# M191C.net
KiCad netlist of a schematic drawn in EAGLE
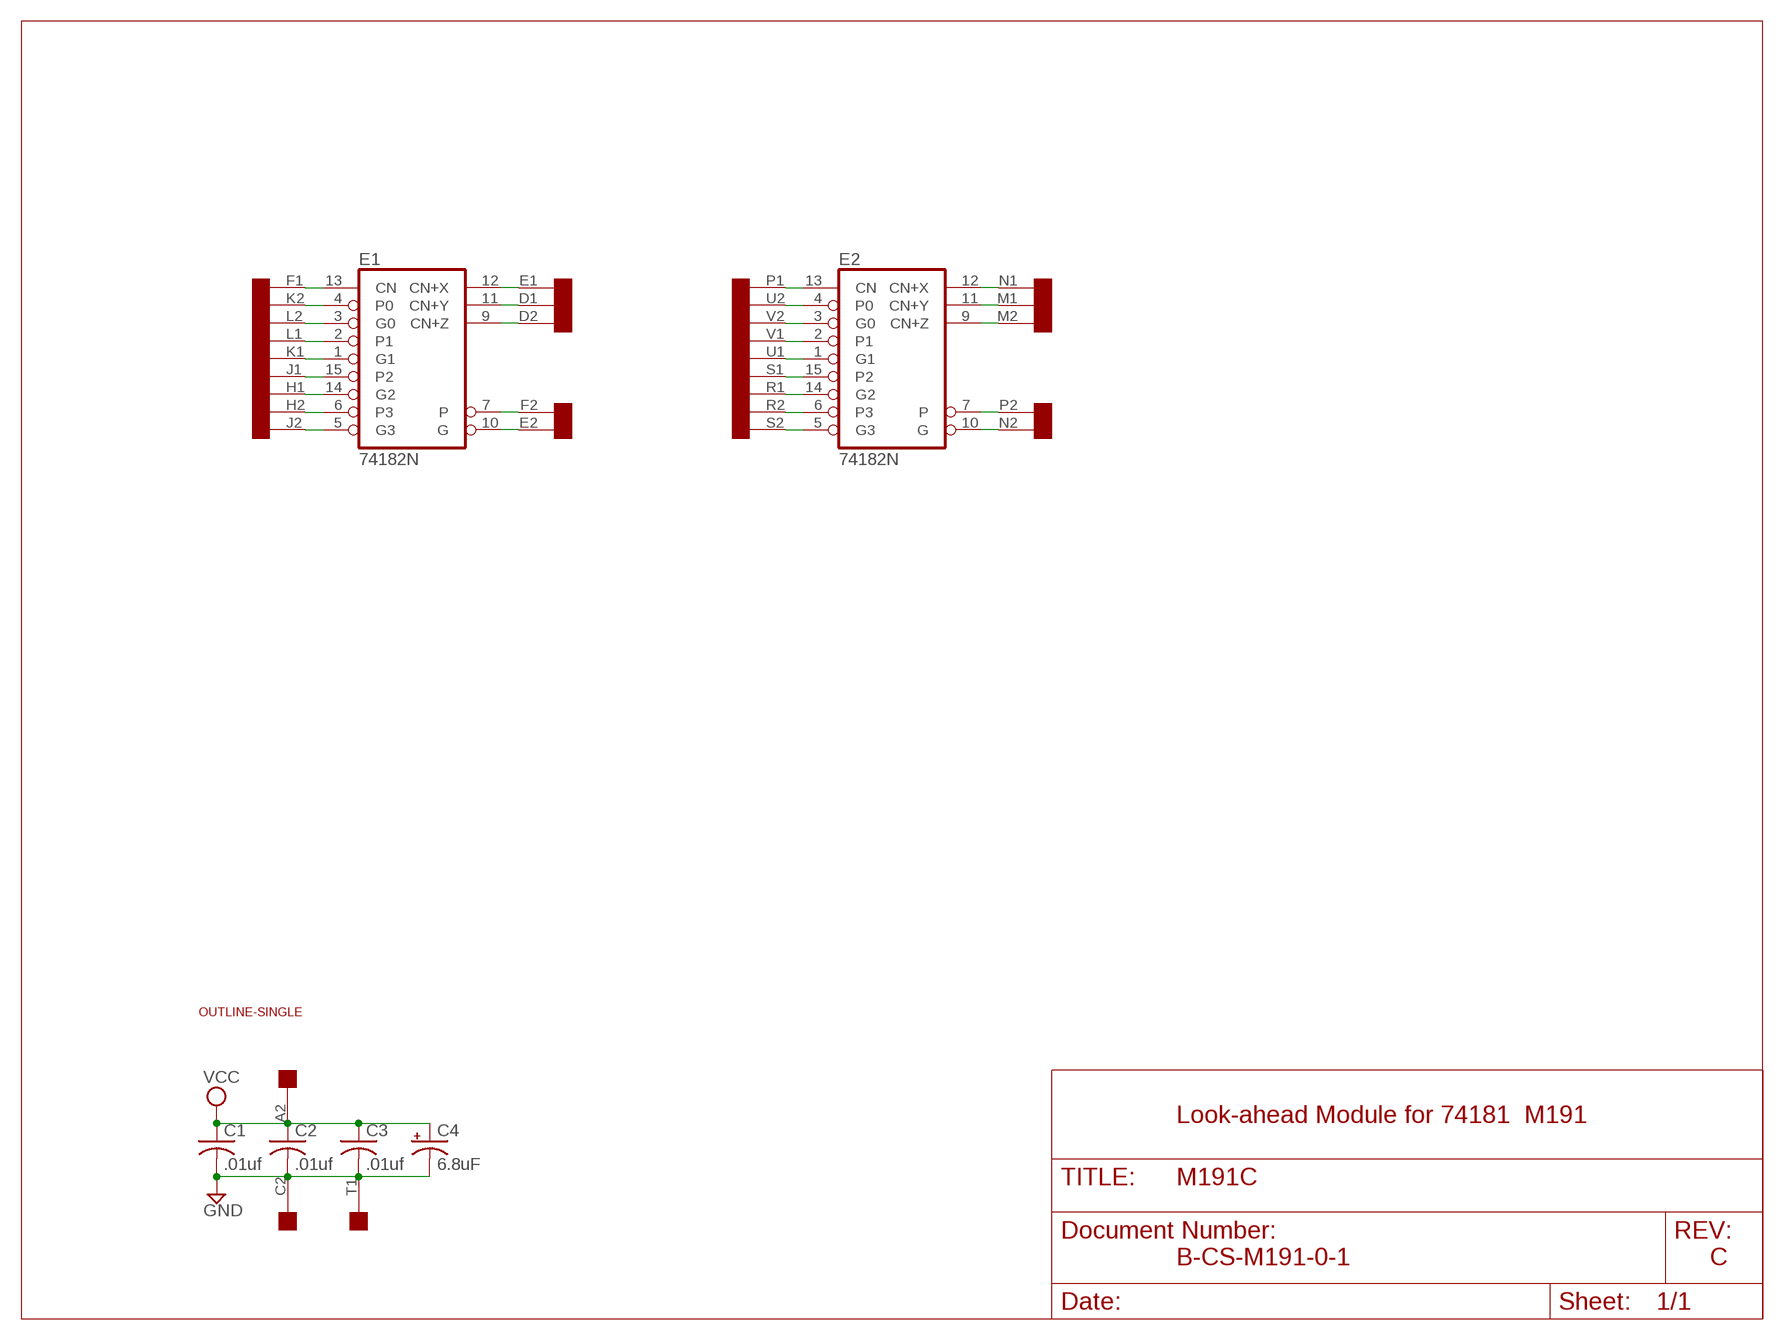
[diagram p0: schematic, sheet 1]

(export (version "E")
  (design (tool "Eeschema 10.0.6"))
  (components
    (comp (ref "C1")
      (value ".01uf")
      (footprint "eagle-import:C050-025X075")
      (libsource (lib "eagle-import") (part "C-US050-025X075"))
    )
    (comp (ref "C2")
      (value ".01uf")
      (footprint "eagle-import:C050-025X075")
      (libsource (lib "eagle-import") (part "C-US050-025X075"))
    )
    (comp (ref "C3")
      (value ".01uf")
      (footprint "eagle-import:C050-025X075")
      (libsource (lib "eagle-import") (part "C-US050-025X075"))
    )
    (comp (ref "C4")
      (value "6.8uF")
      (footprint "eagle-import:E22-6")
      (libsource (lib "eagle-import") (part "CPOL-USE22-6AXIAL"))
    )
    (comp (ref "E1")
      (value "74182N")
      (footprint "eagle-import:DIL16")
      (libsource (lib "eagle-import") (part "74182NS"))
    )
    (comp (ref "E2")
      (value "74182N")
      (footprint "eagle-import:DIL16")
      (libsource (lib "eagle-import") (part "74182NS"))
    )
    (comp (ref "U$1")
      (value "OUTLINE-SINGLE")
      (footprint "eagle-import:SINGLE")
      (libsource (lib "eagle-import") (part "OUTLINE-SINGLE"))
    )
    (comp (ref "U$2")
      (value "EDGE-2CONNECTOR")
      (footprint "eagle-import:EDGE-CON2")
      (libsource (lib "eagle-import") (part "EDGE-2CONNECTOR"))
    )
  )
  (nets
    (net (code "1") (name "GND") (class "Default")
      (node (ref "C1") (pin "2") (pinfunction "2_2") (pintype "passive"))
      (node (ref "C2") (pin "2") (pinfunction "2_2") (pintype "passive"))
      (node (ref "C3") (pin "2") (pinfunction "2_2") (pintype "passive"))
      (node (ref "C4") (pin "-") (pinfunction "-_-") (pintype "passive"))
      (node (ref "U$2") (pin "C2") (pinfunction "1_C2") (pintype "bidirectional"))
      (node (ref "U$2") (pin "T1") (pinfunction "1_T1") (pintype "bidirectional"))
    )
    (net (code "2") (name "Net-(E1A-CN)") (class "Default")
      (node (ref "E1") (pin "13") (pinfunction "CN_13") (pintype "input"))
      (node (ref "U$2") (pin "F1") (pinfunction "1_F1") (pintype "bidirectional"))
    )
    (net (code "3") (name "Net-(E1A-CN+X)") (class "Default")
      (node (ref "E1") (pin "12") (pinfunction "CN+X_12") (pintype "output"))
      (node (ref "U$2") (pin "E1") (pinfunction "1_E1") (pintype "bidirectional"))
    )
    (net (code "4") (name "Net-(E1A-CN+Y)") (class "Default")
      (node (ref "E1") (pin "11") (pinfunction "CN+Y_11") (pintype "output"))
      (node (ref "U$2") (pin "D1") (pinfunction "1_D1") (pintype "bidirectional"))
    )
    (net (code "5") (name "Net-(E1A-CN+Z)") (class "Default")
      (node (ref "E1") (pin "9") (pinfunction "CN+Z_9") (pintype "output"))
      (node (ref "U$2") (pin "D2") (pinfunction "1_D2") (pintype "bidirectional"))
    )
    (net (code "6") (name "Net-(E1A-G)") (class "Default")
      (node (ref "E1") (pin "10") (pinfunction "G_10") (pintype "output"))
      (node (ref "U$2") (pin "E2") (pinfunction "1_E2") (pintype "bidirectional"))
    )
    (net (code "7") (name "Net-(E1A-G0)") (class "Default")
      (node (ref "E1") (pin "3") (pinfunction "G0_3") (pintype "input"))
      (node (ref "U$2") (pin "L2") (pinfunction "1_L2") (pintype "bidirectional"))
    )
    (net (code "8") (name "Net-(E1A-G1)") (class "Default")
      (node (ref "E1") (pin "1") (pinfunction "G1_1") (pintype "input"))
      (node (ref "U$2") (pin "K1") (pinfunction "1_K1") (pintype "bidirectional"))
    )
    (net (code "9") (name "Net-(E1A-G2)") (class "Default")
      (node (ref "E1") (pin "14") (pinfunction "G2_14") (pintype "input"))
      (node (ref "U$2") (pin "H1") (pinfunction "1_H1") (pintype "bidirectional"))
    )
    (net (code "10") (name "Net-(E1A-G3)") (class "Default")
      (node (ref "E1") (pin "5") (pinfunction "G3_5") (pintype "input"))
      (node (ref "U$2") (pin "J2") (pinfunction "1_J2") (pintype "bidirectional"))
    )
    (net (code "11") (name "Net-(E1A-P)") (class "Default")
      (node (ref "E1") (pin "7") (pinfunction "P_7") (pintype "output"))
      (node (ref "U$2") (pin "F2") (pinfunction "1_F2") (pintype "bidirectional"))
    )
    (net (code "12") (name "Net-(E1A-P0)") (class "Default")
      (node (ref "E1") (pin "4") (pinfunction "P0_4") (pintype "input"))
      (node (ref "U$2") (pin "K2") (pinfunction "1_K2") (pintype "bidirectional"))
    )
    (net (code "13") (name "Net-(E1A-P1)") (class "Default")
      (node (ref "E1") (pin "2") (pinfunction "P1_2") (pintype "input"))
      (node (ref "U$2") (pin "L1") (pinfunction "1_L1") (pintype "bidirectional"))
    )
    (net (code "14") (name "Net-(E1A-P2)") (class "Default")
      (node (ref "E1") (pin "15") (pinfunction "P2_15") (pintype "input"))
      (node (ref "U$2") (pin "J1") (pinfunction "1_J1") (pintype "bidirectional"))
    )
    (net (code "15") (name "Net-(E1A-P3)") (class "Default")
      (node (ref "E1") (pin "6") (pinfunction "P3_6") (pintype "input"))
      (node (ref "U$2") (pin "H2") (pinfunction "1_H2") (pintype "bidirectional"))
    )
    (net (code "16") (name "Net-(E2A-CN)") (class "Default")
      (node (ref "E2") (pin "13") (pinfunction "CN_13") (pintype "input"))
      (node (ref "U$2") (pin "P1") (pinfunction "1_P1") (pintype "bidirectional"))
    )
    (net (code "17") (name "Net-(E2A-CN+X)") (class "Default")
      (node (ref "E2") (pin "12") (pinfunction "CN+X_12") (pintype "output"))
      (node (ref "U$2") (pin "N1") (pinfunction "1_N1") (pintype "bidirectional"))
    )
    (net (code "18") (name "Net-(E2A-CN+Y)") (class "Default")
      (node (ref "E2") (pin "11") (pinfunction "CN+Y_11") (pintype "output"))
      (node (ref "U$2") (pin "M1") (pinfunction "1_M1") (pintype "bidirectional"))
    )
    (net (code "19") (name "Net-(E2A-CN+Z)") (class "Default")
      (node (ref "E2") (pin "9") (pinfunction "CN+Z_9") (pintype "output"))
      (node (ref "U$2") (pin "M2") (pinfunction "1_M2") (pintype "bidirectional"))
    )
    (net (code "20") (name "Net-(E2A-G)") (class "Default")
      (node (ref "E2") (pin "10") (pinfunction "G_10") (pintype "output"))
      (node (ref "U$2") (pin "N2") (pinfunction "1_N2") (pintype "bidirectional"))
    )
    (net (code "21") (name "Net-(E2A-G0)") (class "Default")
      (node (ref "E2") (pin "3") (pinfunction "G0_3") (pintype "input"))
      (node (ref "U$2") (pin "V2") (pinfunction "1_V2") (pintype "bidirectional"))
    )
    (net (code "22") (name "Net-(E2A-G1)") (class "Default")
      (node (ref "E2") (pin "1") (pinfunction "G1_1") (pintype "input"))
      (node (ref "U$2") (pin "U1") (pinfunction "1_U1") (pintype "bidirectional"))
    )
    (net (code "23") (name "Net-(E2A-G2)") (class "Default")
      (node (ref "E2") (pin "14") (pinfunction "G2_14") (pintype "input"))
      (node (ref "U$2") (pin "R1") (pinfunction "1_R1") (pintype "bidirectional"))
    )
    (net (code "24") (name "Net-(E2A-G3)") (class "Default")
      (node (ref "E2") (pin "5") (pinfunction "G3_5") (pintype "input"))
      (node (ref "U$2") (pin "S2") (pinfunction "1_S2") (pintype "bidirectional"))
    )
    (net (code "25") (name "Net-(E2A-P)") (class "Default")
      (node (ref "E2") (pin "7") (pinfunction "P_7") (pintype "output"))
      (node (ref "U$2") (pin "P2") (pinfunction "1_P2") (pintype "bidirectional"))
    )
    (net (code "26") (name "Net-(E2A-P0)") (class "Default")
      (node (ref "E2") (pin "4") (pinfunction "P0_4") (pintype "input"))
      (node (ref "U$2") (pin "U2") (pinfunction "1_U2") (pintype "bidirectional"))
    )
    (net (code "27") (name "Net-(E2A-P1)") (class "Default")
      (node (ref "E2") (pin "2") (pinfunction "P1_2") (pintype "input"))
      (node (ref "U$2") (pin "V1") (pinfunction "1_V1") (pintype "bidirectional"))
    )
    (net (code "28") (name "Net-(E2A-P2)") (class "Default")
      (node (ref "E2") (pin "15") (pinfunction "P2_15") (pintype "input"))
      (node (ref "U$2") (pin "S1") (pinfunction "1_S1") (pintype "bidirectional"))
    )
    (net (code "29") (name "Net-(E2A-P3)") (class "Default")
      (node (ref "E2") (pin "6") (pinfunction "P3_6") (pintype "input"))
      (node (ref "U$2") (pin "R2") (pinfunction "1_R2") (pintype "bidirectional"))
    )
    (net (code "30") (name "VCC") (class "Default")
      (node (ref "C1") (pin "1") (pinfunction "1_1") (pintype "passive"))
      (node (ref "C2") (pin "1") (pinfunction "1_1") (pintype "passive"))
      (node (ref "C3") (pin "1") (pinfunction "1_1") (pintype "passive"))
      (node (ref "C4") (pin "+") (pinfunction "+_+") (pintype "passive"))
      (node (ref "U$2") (pin "A2") (pinfunction "1_A2") (pintype "bidirectional"))
    )
  )
)
